# untitled.net
KiCad netlist of a schematic drawn in EAGLE
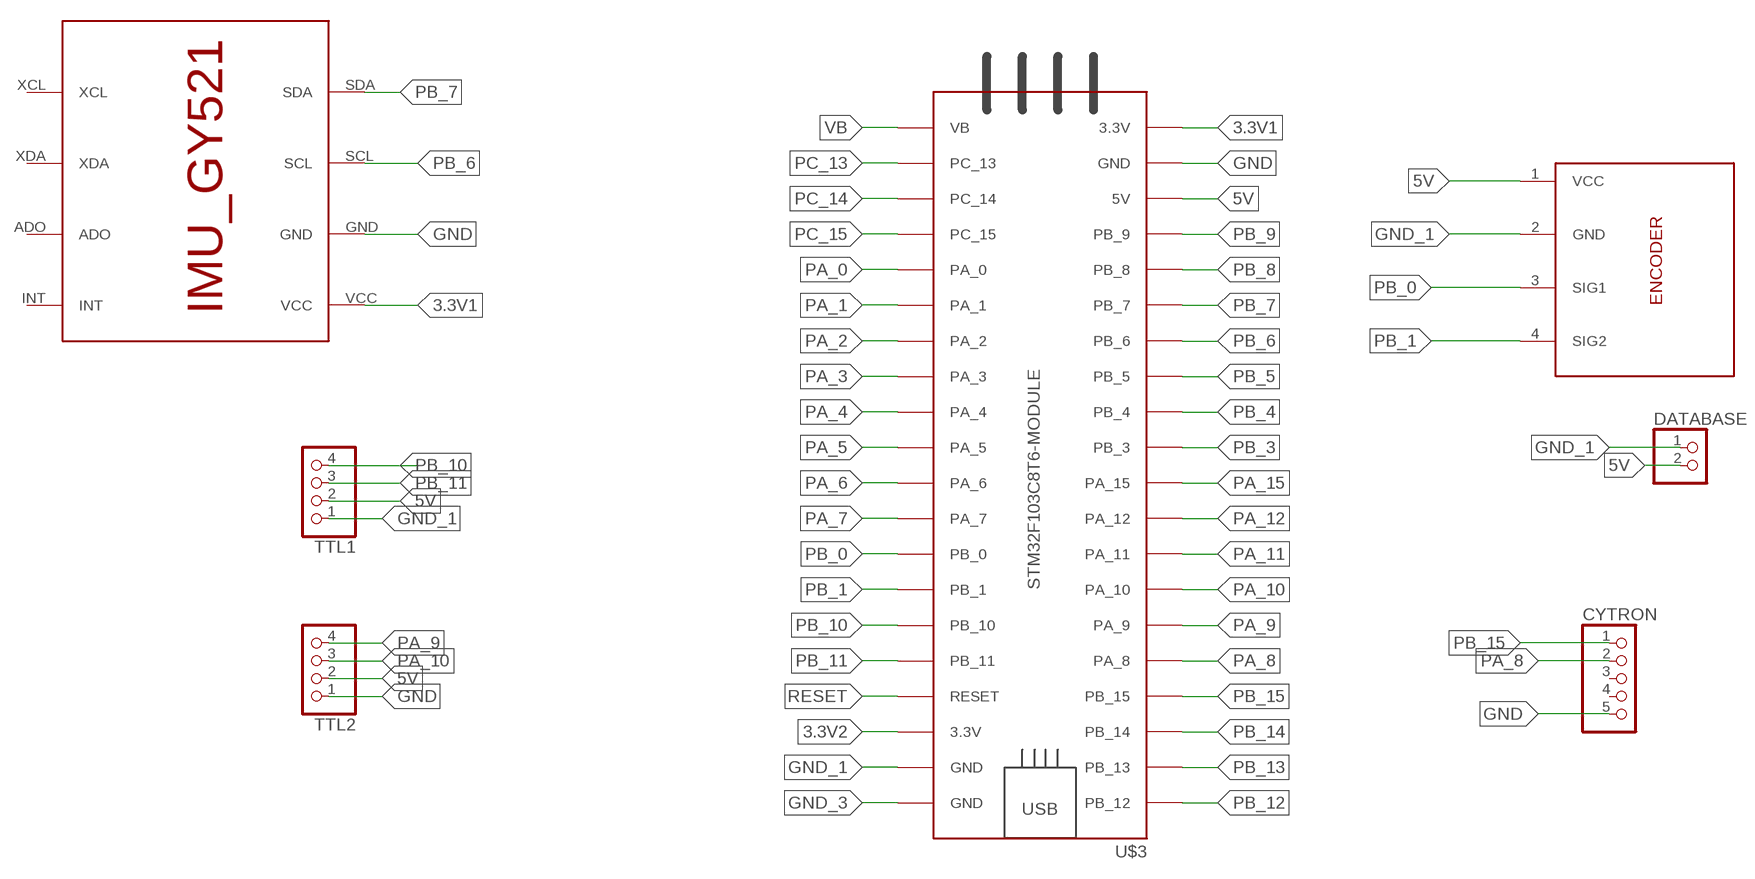
[diagram p0: schematic, sheet 1]

(export (version "E")
  (design (tool "Eeschema 10.0.6"))
  (components
    (comp (ref "CYTRON")
      (value "PINHD-1X5")
      (footprint "eagle-import:1X05")
      (libsource (lib "eagle-import") (part "PINHD-1X5"))
    )
    (comp (ref "DATABASE")
      (value "PINHD-2_DATA")
      (footprint "eagle-import:1X02_DATA")
      (libsource (lib "eagle-import") (part "PINHD-2_DATA"))
    )
    (comp (ref "TTL1")
      (value "PINHD-1X4")
      (footprint "eagle-import:1X04")
      (libsource (lib "eagle-import") (part "PINHD-1X4"))
    )
    (comp (ref "TTL2")
      (value "PINHD-1X4")
      (footprint "eagle-import:1X04")
      (libsource (lib "eagle-import") (part "PINHD-1X4"))
    )
    (comp (ref "U$1")
      (value "ENCODER")
      (footprint "eagle-import:1X04_DATA")
      (libsource (lib "eagle-import") (part "ENCODER"))
    )
    (comp (ref "U$2")
      (value "IMU_ROBOCON_GY521")
      (footprint "eagle-import:IMU_GY521")
      (libsource (lib "eagle-import") (part "IMU_ROBOCON_GY521"))
    )
    (comp (ref "U$3")
      (value "STM32F103C8T6-MODULE")
      (footprint "eagle-import:STM32F103C8T6-MODULE")
      (libsource (lib "eagle-import") (part "STM32F103C8T6-MODULE"))
    )
  )
  (nets
    (net (code "1") (name "3.3V1") (class "Default")
      (node (ref "U$2") (pin "VCC") (pinfunction "VCC_VCC") (pintype "bidirectional"))
      (node (ref "U$3") (pin "3.3V_1") (pinfunction "3.3V_3.3V_1") (pintype "bidirectional"))
    )
    (net (code "2") (name "3.3V2") (class "Default")
      (node (ref "U$3") (pin "3.3V_2") (pinfunction "3.3V_3.3V_2") (pintype "bidirectional"))
    )
    (net (code "3") (name "5V") (class "Default")
      (node (ref "DATABASE") (pin "2") (pinfunction "2_2") (pintype "passive"))
      (node (ref "TTL1") (pin "2") (pinfunction "2_2") (pintype "passive"))
      (node (ref "TTL2") (pin "2") (pinfunction "2_2") (pintype "passive"))
      (node (ref "U$1") (pin "1") (pinfunction "VCC_1") (pintype "bidirectional"))
      (node (ref "U$3") (pin "5V") (pinfunction "5V_5V") (pintype "bidirectional"))
    )
    (net (code "4") (name "GND") (class "Default")
      (node (ref "CYTRON") (pin "5") (pinfunction "5_5") (pintype "passive"))
      (node (ref "TTL2") (pin "1") (pinfunction "1_1") (pintype "passive"))
      (node (ref "U$2") (pin "GND") (pinfunction "GND_GND") (pintype "bidirectional"))
      (node (ref "U$3") (pin "GND_1") (pinfunction "GND_GND_1") (pintype "bidirectional"))
    )
    (net (code "5") (name "GND_1") (class "Default")
      (node (ref "DATABASE") (pin "1") (pinfunction "1_1") (pintype "passive"))
      (node (ref "TTL1") (pin "1") (pinfunction "1_1") (pintype "passive"))
      (node (ref "U$1") (pin "2") (pinfunction "GND_2") (pintype "bidirectional"))
      (node (ref "U$3") (pin "GND_2") (pinfunction "GND_GND_2") (pintype "bidirectional"))
    )
    (net (code "6") (name "GND_3") (class "Default")
      (node (ref "U$3") (pin "GND_3") (pinfunction "GND_GND_3") (pintype "power_in"))
    )
    (net (code "7") (name "PA_0") (class "Default")
      (node (ref "U$3") (pin "PA_0") (pinfunction "PA_0_PA_0") (pintype "bidirectional"))
    )
    (net (code "8") (name "PA_1") (class "Default")
      (node (ref "U$3") (pin "PA_1") (pinfunction "PA_1_PA_1") (pintype "bidirectional"))
    )
    (net (code "9") (name "PA_2") (class "Default")
      (node (ref "U$3") (pin "PA_2") (pinfunction "PA_2_PA_2") (pintype "bidirectional"))
    )
    (net (code "10") (name "PA_3") (class "Default")
      (node (ref "U$3") (pin "PA_3") (pinfunction "PA_3_PA_3") (pintype "bidirectional"))
    )
    (net (code "11") (name "PA_4") (class "Default")
      (node (ref "U$3") (pin "PA_4") (pinfunction "PA_4_PA_4") (pintype "bidirectional"))
    )
    (net (code "12") (name "PA_5") (class "Default")
      (node (ref "U$3") (pin "PA_5") (pinfunction "PA_5_PA_5") (pintype "bidirectional"))
    )
    (net (code "13") (name "PA_6") (class "Default")
      (node (ref "U$3") (pin "PA_6") (pinfunction "PA_6_PA_6") (pintype "bidirectional"))
    )
    (net (code "14") (name "PA_7") (class "Default")
      (node (ref "U$3") (pin "PA_7") (pinfunction "PA_7_PA_7") (pintype "bidirectional"))
    )
    (net (code "15") (name "PA_8") (class "Default")
      (node (ref "CYTRON") (pin "2") (pinfunction "2_2") (pintype "passive"))
      (node (ref "U$3") (pin "PA_8") (pinfunction "PA_8_PA_8") (pintype "bidirectional"))
    )
    (net (code "16") (name "PA_9") (class "Default")
      (node (ref "TTL2") (pin "4") (pinfunction "4_4") (pintype "passive"))
      (node (ref "U$3") (pin "PA_9") (pinfunction "PA_9_PA_9") (pintype "bidirectional"))
    )
    (net (code "17") (name "PA_10") (class "Default")
      (node (ref "TTL2") (pin "3") (pinfunction "3_3") (pintype "passive"))
      (node (ref "U$3") (pin "PA_10") (pinfunction "PA_10_PA_10") (pintype "bidirectional"))
    )
    (net (code "18") (name "PA_11") (class "Default")
      (node (ref "U$3") (pin "PA_11") (pinfunction "PA_11_PA_11") (pintype "bidirectional"))
    )
    (net (code "19") (name "PA_12") (class "Default")
      (node (ref "U$3") (pin "PA_12") (pinfunction "PA_12_PA_12") (pintype "bidirectional"))
    )
    (net (code "20") (name "PA_15") (class "Default")
      (node (ref "U$3") (pin "PA_15") (pinfunction "PA_15_PA_15") (pintype "bidirectional"))
    )
    (net (code "21") (name "PB_0") (class "Default")
      (node (ref "U$1") (pin "3") (pinfunction "SIG1_3") (pintype "bidirectional"))
      (node (ref "U$3") (pin "PB_0") (pinfunction "PB_0_PB_0") (pintype "bidirectional"))
    )
    (net (code "22") (name "PB_1") (class "Default")
      (node (ref "U$1") (pin "4") (pinfunction "SIG2_4") (pintype "bidirectional"))
      (node (ref "U$3") (pin "PB_1") (pinfunction "PB_1_PB_1") (pintype "bidirectional"))
    )
    (net (code "23") (name "PB_3") (class "Default")
      (node (ref "U$3") (pin "PB_3") (pinfunction "PB_3_PB_3") (pintype "bidirectional"))
    )
    (net (code "24") (name "PB_4") (class "Default")
      (node (ref "U$3") (pin "PB_4") (pinfunction "PB_4_PB_4") (pintype "bidirectional"))
    )
    (net (code "25") (name "PB_5") (class "Default")
      (node (ref "U$3") (pin "PB_5") (pinfunction "PB_5_PB_5") (pintype "bidirectional"))
    )
    (net (code "26") (name "PB_6") (class "Default")
      (node (ref "U$2") (pin "SCL") (pinfunction "SCL_SCL") (pintype "bidirectional"))
      (node (ref "U$3") (pin "PB_6") (pinfunction "PB_6_PB_6") (pintype "bidirectional"))
    )
    (net (code "27") (name "PB_7") (class "Default")
      (node (ref "U$2") (pin "SDA") (pinfunction "SDA_SDA") (pintype "bidirectional"))
      (node (ref "U$3") (pin "PB_7") (pinfunction "PB_7_PB_7") (pintype "bidirectional"))
    )
    (net (code "28") (name "PB_8") (class "Default")
      (node (ref "U$3") (pin "PB_8") (pinfunction "PB_8_PB_8") (pintype "bidirectional"))
    )
    (net (code "29") (name "PB_9") (class "Default")
      (node (ref "U$3") (pin "PB_9") (pinfunction "PB_9_PB_9") (pintype "bidirectional"))
    )
    (net (code "30") (name "PB_10") (class "Default")
      (node (ref "TTL1") (pin "4") (pinfunction "4_4") (pintype "passive"))
      (node (ref "U$3") (pin "PB_10") (pinfunction "PB_10_PB_10") (pintype "bidirectional"))
    )
    (net (code "31") (name "PB_11") (class "Default")
      (node (ref "TTL1") (pin "3") (pinfunction "3_3") (pintype "passive"))
      (node (ref "U$3") (pin "PB_11") (pinfunction "PB_11_PB_11") (pintype "bidirectional"))
    )
    (net (code "32") (name "PB_12") (class "Default")
      (node (ref "U$3") (pin "PB_12") (pinfunction "PB_12_PB_12") (pintype "bidirectional"))
    )
    (net (code "33") (name "PB_13") (class "Default")
      (node (ref "U$3") (pin "PB_13") (pinfunction "PB_13_PB_13") (pintype "bidirectional"))
    )
    (net (code "34") (name "PB_14") (class "Default")
      (node (ref "U$3") (pin "PB_14") (pinfunction "PB_14_PB_14") (pintype "bidirectional"))
    )
    (net (code "35") (name "PB_15") (class "Default")
      (node (ref "CYTRON") (pin "1") (pinfunction "1_1") (pintype "passive"))
      (node (ref "U$3") (pin "PB_15") (pinfunction "PB_15_PB_15") (pintype "bidirectional"))
    )
    (net (code "36") (name "PC_13") (class "Default")
      (node (ref "U$3") (pin "PC_13") (pinfunction "PC_13_PC_13") (pintype "bidirectional"))
    )
    (net (code "37") (name "PC_14") (class "Default")
      (node (ref "U$3") (pin "PC_14") (pinfunction "PC_14_PC_14") (pintype "bidirectional"))
    )
    (net (code "38") (name "PC_15") (class "Default")
      (node (ref "U$3") (pin "PC_15") (pinfunction "PC_15_PC_15") (pintype "bidirectional"))
    )
    (net (code "39") (name "RESET") (class "Default")
      (node (ref "U$3") (pin "RESET") (pinfunction "RESET_RESET") (pintype "bidirectional"))
    )
    (net (code "40") (name "VB") (class "Default")
      (node (ref "U$3") (pin "VB") (pinfunction "VB_VB") (pintype "bidirectional"))
    )
    (net (code "41") (name "unconnected-(CYTRON-Pad3)") (class "Default")
      (node (ref "CYTRON") (pin "3") (pinfunction "3_3") (pintype "passive"))
    )
    (net (code "42") (name "unconnected-(CYTRON-Pad4)") (class "Default")
      (node (ref "CYTRON") (pin "4") (pinfunction "4_4") (pintype "passive"))
    )
    (net (code "43") (name "unconnected-(U$2-PadADO)") (class "Default")
      (node (ref "U$2") (pin "ADO") (pinfunction "ADO_ADO") (pintype "bidirectional"))
    )
    (net (code "44") (name "unconnected-(U$2-PadINT)") (class "Default")
      (node (ref "U$2") (pin "INT") (pinfunction "INT_INT") (pintype "bidirectional"))
    )
    (net (code "45") (name "unconnected-(U$2-PadXCL)") (class "Default")
      (node (ref "U$2") (pin "XCL") (pinfunction "XCL_XCL") (pintype "bidirectional"))
    )
    (net (code "46") (name "unconnected-(U$2-PadXDA)") (class "Default")
      (node (ref "U$2") (pin "XDA") (pinfunction "XDA_XDA") (pintype "bidirectional"))
    )
  )
)
